# LCs.net
KiCad netlist of a schematic drawn in Altium Designer
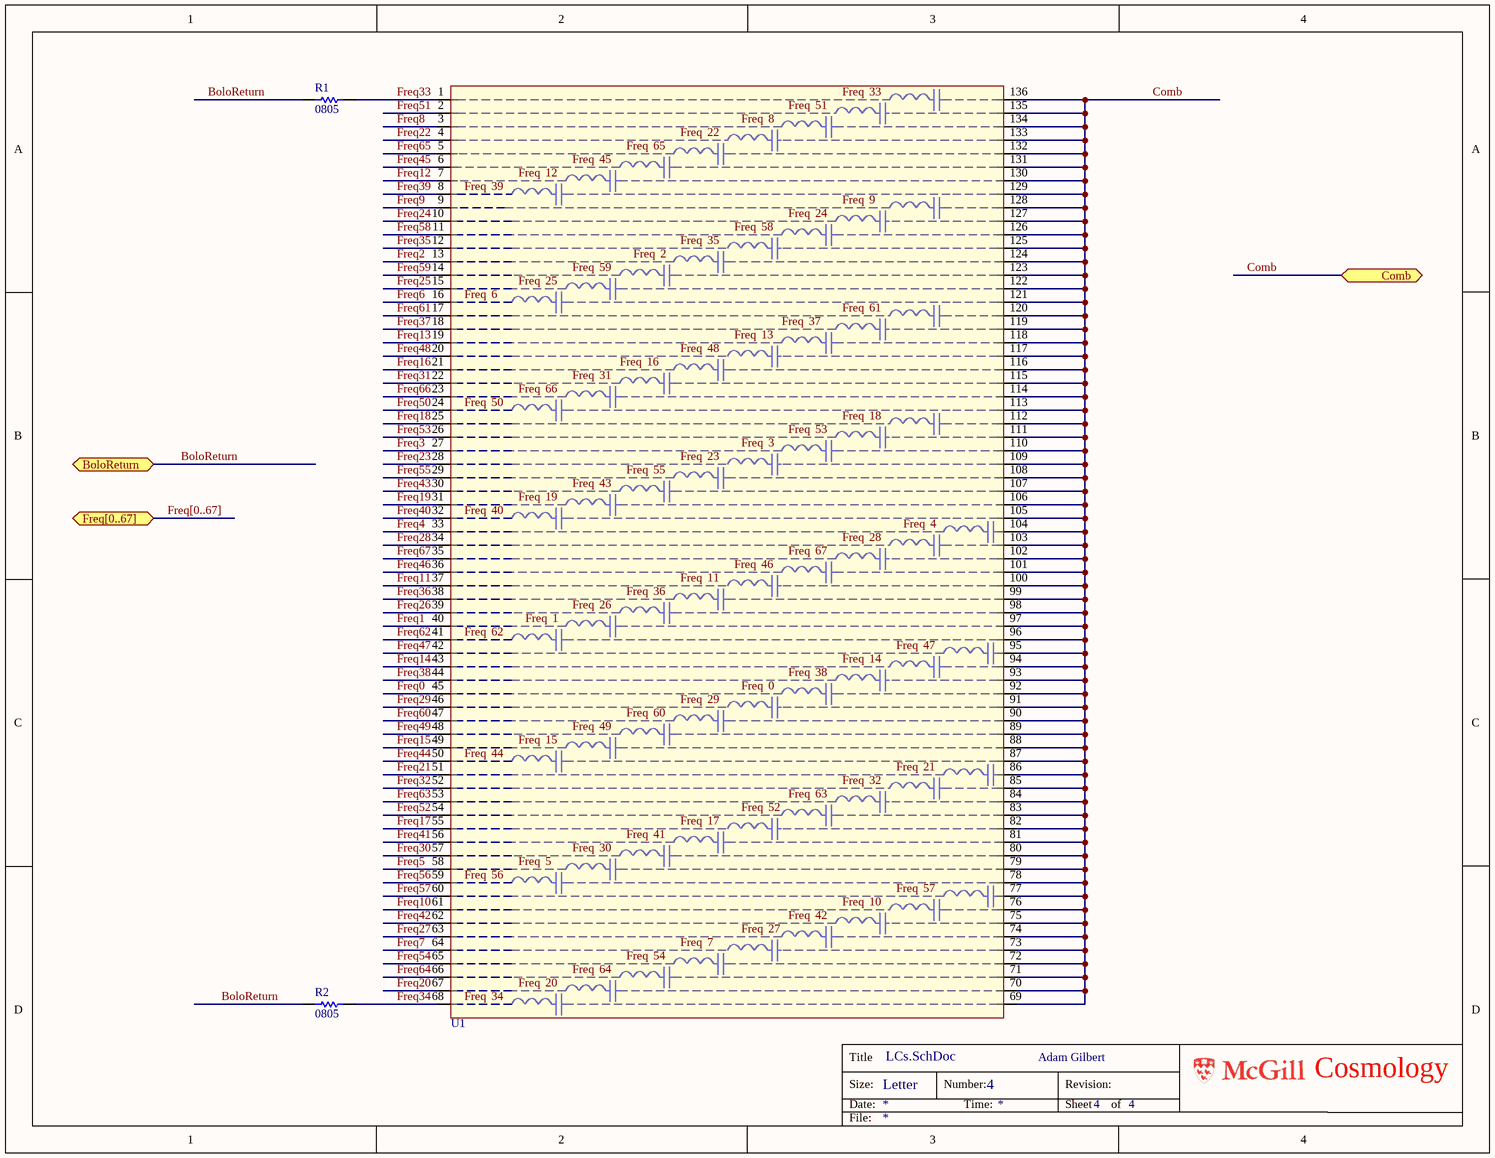
[diagram p0: LCs.SchDoc]

(export (version "E")
  (design (tool "Eeschema 10.0.6"))
  (components
    (comp (ref "R1")
      (value "Res1206")
      (footprint "0805")
      (description "Resistor")
      (libsource (lib "SPT3G_LCBoard") (part "Res1206"))
    )
    (comp (ref "R2")
      (value "Res1206")
      (footprint "0805")
      (description "Resistor")
      (libsource (lib "SPT3G_LCBoard") (part "Res1206"))
    )
    (comp (ref "U1")
      (value "LC68_wafer")
      (footprint "68xLC")
      (description "Gold bonded integrated LC")
      (libsource (lib "SPT3G_LCBoard") (part "LC68Wafer"))
    )
  )
  (nets
    (net (code "1") (name "/BoloReturn") (class "Default")
      (node (ref "R1") (pin "1") (pinfunction "1_1") (pintype "passive"))
      (node (ref "R2") (pin "1") (pinfunction "1_1") (pintype "passive"))
    )
    (net (code "2") (name "/Comb") (class "Default")
      (node (ref "U1") (pin "100") (pinfunction "100_100") (pintype "passive"))
      (node (ref "U1") (pin "101") (pinfunction "101_101") (pintype "passive"))
      (node (ref "U1") (pin "102") (pinfunction "102_102") (pintype "passive"))
      (node (ref "U1") (pin "103") (pinfunction "103_103") (pintype "passive"))
      (node (ref "U1") (pin "104") (pinfunction "104_104") (pintype "passive"))
      (node (ref "U1") (pin "105") (pinfunction "105_105") (pintype "passive"))
      (node (ref "U1") (pin "106") (pinfunction "106_106") (pintype "passive"))
      (node (ref "U1") (pin "107") (pinfunction "107_107") (pintype "passive"))
      (node (ref "U1") (pin "108") (pinfunction "108_108") (pintype "passive"))
      (node (ref "U1") (pin "109") (pinfunction "109_109") (pintype "passive"))
      (node (ref "U1") (pin "110") (pinfunction "110_110") (pintype "passive"))
      (node (ref "U1") (pin "111") (pinfunction "111_111") (pintype "passive"))
      (node (ref "U1") (pin "112") (pinfunction "112_112") (pintype "passive"))
      (node (ref "U1") (pin "113") (pinfunction "113_113") (pintype "passive"))
      (node (ref "U1") (pin "114") (pinfunction "114_114") (pintype "passive"))
      (node (ref "U1") (pin "115") (pinfunction "115_115") (pintype "passive"))
      (node (ref "U1") (pin "116") (pinfunction "116_116") (pintype "passive"))
      (node (ref "U1") (pin "117") (pinfunction "117_117") (pintype "passive"))
      (node (ref "U1") (pin "118") (pinfunction "118_118") (pintype "passive"))
      (node (ref "U1") (pin "119") (pinfunction "119_119") (pintype "passive"))
      (node (ref "U1") (pin "120") (pinfunction "120_120") (pintype "passive"))
      (node (ref "U1") (pin "121") (pinfunction "121_121") (pintype "passive"))
      (node (ref "U1") (pin "122") (pinfunction "122_122") (pintype "passive"))
      (node (ref "U1") (pin "123") (pinfunction "123_123") (pintype "passive"))
      (node (ref "U1") (pin "124") (pinfunction "124_124") (pintype "passive"))
      (node (ref "U1") (pin "125") (pinfunction "125_125") (pintype "passive"))
      (node (ref "U1") (pin "126") (pinfunction "126_126") (pintype "passive"))
      (node (ref "U1") (pin "127") (pinfunction "127_127") (pintype "passive"))
      (node (ref "U1") (pin "128") (pinfunction "128_128") (pintype "passive"))
      (node (ref "U1") (pin "129") (pinfunction "129_129") (pintype "passive"))
      (node (ref "U1") (pin "130") (pinfunction "130_130") (pintype "passive"))
      (node (ref "U1") (pin "131") (pinfunction "131_131") (pintype "passive"))
      (node (ref "U1") (pin "132") (pinfunction "132_132") (pintype "passive"))
      (node (ref "U1") (pin "133") (pinfunction "133_133") (pintype "passive"))
      (node (ref "U1") (pin "134") (pinfunction "134_134") (pintype "passive"))
      (node (ref "U1") (pin "135") (pinfunction "135_135") (pintype "passive"))
      (node (ref "U1") (pin "136") (pinfunction "136_136") (pintype "passive"))
      (node (ref "U1") (pin "69") (pinfunction "69_69") (pintype "passive"))
      (node (ref "U1") (pin "70") (pinfunction "70_70") (pintype "passive"))
      (node (ref "U1") (pin "71") (pinfunction "71_71") (pintype "passive"))
      (node (ref "U1") (pin "72") (pinfunction "72_72") (pintype "passive"))
      (node (ref "U1") (pin "73") (pinfunction "73_73") (pintype "passive"))
      (node (ref "U1") (pin "74") (pinfunction "74_74") (pintype "passive"))
      (node (ref "U1") (pin "75") (pinfunction "75_75") (pintype "passive"))
      (node (ref "U1") (pin "76") (pinfunction "76_76") (pintype "passive"))
      (node (ref "U1") (pin "77") (pinfunction "77_77") (pintype "passive"))
      (node (ref "U1") (pin "78") (pinfunction "78_78") (pintype "passive"))
      (node (ref "U1") (pin "79") (pinfunction "79_79") (pintype "passive"))
      (node (ref "U1") (pin "80") (pinfunction "80_80") (pintype "passive"))
      (node (ref "U1") (pin "81") (pinfunction "81_81") (pintype "passive"))
      (node (ref "U1") (pin "82") (pinfunction "82_82") (pintype "passive"))
      (node (ref "U1") (pin "83") (pinfunction "83_83") (pintype "passive"))
      (node (ref "U1") (pin "84") (pinfunction "84_84") (pintype "passive"))
      (node (ref "U1") (pin "85") (pinfunction "85_85") (pintype "passive"))
      (node (ref "U1") (pin "86") (pinfunction "86_86") (pintype "passive"))
      (node (ref "U1") (pin "87") (pinfunction "87_87") (pintype "passive"))
      (node (ref "U1") (pin "88") (pinfunction "88_88") (pintype "passive"))
      (node (ref "U1") (pin "89") (pinfunction "89_89") (pintype "passive"))
      (node (ref "U1") (pin "90") (pinfunction "90_90") (pintype "passive"))
      (node (ref "U1") (pin "91") (pinfunction "91_91") (pintype "passive"))
      (node (ref "U1") (pin "92") (pinfunction "92_92") (pintype "passive"))
      (node (ref "U1") (pin "93") (pinfunction "93_93") (pintype "passive"))
      (node (ref "U1") (pin "94") (pinfunction "94_94") (pintype "passive"))
      (node (ref "U1") (pin "95") (pinfunction "95_95") (pintype "passive"))
      (node (ref "U1") (pin "96") (pinfunction "96_96") (pintype "passive"))
      (node (ref "U1") (pin "97") (pinfunction "97_97") (pintype "passive"))
      (node (ref "U1") (pin "98") (pinfunction "98_98") (pintype "passive"))
      (node (ref "U1") (pin "99") (pinfunction "99_99") (pintype "passive"))
    )
    (net (code "3") (name "/Freq0") (class "Default")
      (node (ref "U1") (pin "45") (pinfunction "45_45") (pintype "passive"))
    )
    (net (code "4") (name "/Freq1") (class "Default")
      (node (ref "U1") (pin "40") (pinfunction "40_40") (pintype "passive"))
    )
    (net (code "5") (name "/Freq2") (class "Default")
      (node (ref "U1") (pin "13") (pinfunction "13_13") (pintype "passive"))
    )
    (net (code "6") (name "/Freq3") (class "Default")
      (node (ref "U1") (pin "27") (pinfunction "27_27") (pintype "passive"))
    )
    (net (code "7") (name "/Freq4") (class "Default")
      (node (ref "U1") (pin "33") (pinfunction "33_33") (pintype "passive"))
    )
    (net (code "8") (name "/Freq5") (class "Default")
      (node (ref "U1") (pin "58") (pinfunction "58_58") (pintype "passive"))
    )
    (net (code "9") (name "/Freq6") (class "Default")
      (node (ref "U1") (pin "16") (pinfunction "16_16") (pintype "passive"))
    )
    (net (code "10") (name "/Freq7") (class "Default")
      (node (ref "U1") (pin "64") (pinfunction "64_64") (pintype "passive"))
    )
    (net (code "11") (name "/Freq8") (class "Default")
      (node (ref "U1") (pin "3") (pinfunction "3_3") (pintype "passive"))
    )
    (net (code "12") (name "/Freq9") (class "Default")
      (node (ref "U1") (pin "9") (pinfunction "9_9") (pintype "passive"))
    )
    (net (code "13") (name "/Freq10") (class "Default")
      (node (ref "U1") (pin "61") (pinfunction "61_61") (pintype "passive"))
    )
    (net (code "14") (name "/Freq11") (class "Default")
      (node (ref "U1") (pin "37") (pinfunction "37_37") (pintype "passive"))
    )
    (net (code "15") (name "/Freq12") (class "Default")
      (node (ref "U1") (pin "7") (pinfunction "7_7") (pintype "passive"))
    )
    (net (code "16") (name "/Freq13") (class "Default")
      (node (ref "U1") (pin "19") (pinfunction "19_19") (pintype "passive"))
    )
    (net (code "17") (name "/Freq14") (class "Default")
      (node (ref "U1") (pin "43") (pinfunction "43_43") (pintype "passive"))
    )
    (net (code "18") (name "/Freq15") (class "Default")
      (node (ref "U1") (pin "49") (pinfunction "49_49") (pintype "passive"))
    )
    (net (code "19") (name "/Freq16") (class "Default")
      (node (ref "U1") (pin "21") (pinfunction "21_21") (pintype "passive"))
    )
    (net (code "20") (name "/Freq17") (class "Default")
      (node (ref "U1") (pin "55") (pinfunction "55_55") (pintype "passive"))
    )
    (net (code "21") (name "/Freq18") (class "Default")
      (node (ref "U1") (pin "25") (pinfunction "25_25") (pintype "passive"))
    )
    (net (code "22") (name "/Freq19") (class "Default")
      (node (ref "U1") (pin "31") (pinfunction "31_31") (pintype "passive"))
    )
    (net (code "23") (name "/Freq20") (class "Default")
      (node (ref "U1") (pin "67") (pinfunction "67_67") (pintype "passive"))
    )
    (net (code "24") (name "/Freq21") (class "Default")
      (node (ref "U1") (pin "51") (pinfunction "51_51") (pintype "passive"))
    )
    (net (code "25") (name "/Freq22") (class "Default")
      (node (ref "U1") (pin "4") (pinfunction "4_4") (pintype "passive"))
    )
    (net (code "26") (name "/Freq23") (class "Default")
      (node (ref "U1") (pin "28") (pinfunction "28_28") (pintype "passive"))
    )
    (net (code "27") (name "/Freq24") (class "Default")
      (node (ref "U1") (pin "10") (pinfunction "10_10") (pintype "passive"))
    )
    (net (code "28") (name "/Freq25") (class "Default")
      (node (ref "U1") (pin "15") (pinfunction "15_15") (pintype "passive"))
    )
    (net (code "29") (name "/Freq26") (class "Default")
      (node (ref "U1") (pin "39") (pinfunction "39_39") (pintype "passive"))
    )
    (net (code "30") (name "/Freq27") (class "Default")
      (node (ref "U1") (pin "63") (pinfunction "63_63") (pintype "passive"))
    )
    (net (code "31") (name "/Freq28") (class "Default")
      (node (ref "U1") (pin "34") (pinfunction "34_34") (pintype "passive"))
    )
    (net (code "32") (name "/Freq29") (class "Default")
      (node (ref "U1") (pin "46") (pinfunction "46_46") (pintype "passive"))
    )
    (net (code "33") (name "/Freq30") (class "Default")
      (node (ref "U1") (pin "57") (pinfunction "57_57") (pintype "passive"))
    )
    (net (code "34") (name "/Freq31") (class "Default")
      (node (ref "U1") (pin "22") (pinfunction "22_22") (pintype "passive"))
    )
    (net (code "35") (name "/Freq32") (class "Default")
      (node (ref "U1") (pin "52") (pinfunction "52_52") (pintype "passive"))
    )
    (net (code "36") (name "/Freq33") (class "Default")
      (node (ref "R1") (pin "2") (pinfunction "2_2") (pintype "passive"))
      (node (ref "U1") (pin "1") (pinfunction "1_1") (pintype "passive"))
    )
    (net (code "37") (name "/Freq34") (class "Default")
      (node (ref "R2") (pin "2") (pinfunction "2_2") (pintype "passive"))
      (node (ref "U1") (pin "68") (pinfunction "68_68") (pintype "passive"))
    )
    (net (code "38") (name "/Freq35") (class "Default")
      (node (ref "U1") (pin "12") (pinfunction "12_12") (pintype "passive"))
    )
    (net (code "39") (name "/Freq36") (class "Default")
      (node (ref "U1") (pin "38") (pinfunction "38_38") (pintype "passive"))
    )
    (net (code "40") (name "/Freq37") (class "Default")
      (node (ref "U1") (pin "18") (pinfunction "18_18") (pintype "passive"))
    )
    (net (code "41") (name "/Freq38") (class "Default")
      (node (ref "U1") (pin "44") (pinfunction "44_44") (pintype "passive"))
    )
    (net (code "42") (name "/Freq39") (class "Default")
      (node (ref "U1") (pin "8") (pinfunction "8_8") (pintype "passive"))
    )
    (net (code "43") (name "/Freq40") (class "Default")
      (node (ref "U1") (pin "32") (pinfunction "32_32") (pintype "passive"))
    )
    (net (code "44") (name "/Freq41") (class "Default")
      (node (ref "U1") (pin "56") (pinfunction "56_56") (pintype "passive"))
    )
    (net (code "45") (name "/Freq42") (class "Default")
      (node (ref "U1") (pin "62") (pinfunction "62_62") (pintype "passive"))
    )
    (net (code "46") (name "/Freq43") (class "Default")
      (node (ref "U1") (pin "30") (pinfunction "30_30") (pintype "passive"))
    )
    (net (code "47") (name "/Freq44") (class "Default")
      (node (ref "U1") (pin "50") (pinfunction "50_50") (pintype "passive"))
    )
    (net (code "48") (name "/Freq45") (class "Default")
      (node (ref "U1") (pin "6") (pinfunction "6_6") (pintype "passive"))
    )
    (net (code "49") (name "/Freq46") (class "Default")
      (node (ref "U1") (pin "36") (pinfunction "36_36") (pintype "passive"))
    )
    (net (code "50") (name "/Freq47") (class "Default")
      (node (ref "U1") (pin "42") (pinfunction "42_42") (pintype "passive"))
    )
    (net (code "51") (name "/Freq48") (class "Default")
      (node (ref "U1") (pin "20") (pinfunction "20_20") (pintype "passive"))
    )
    (net (code "52") (name "/Freq49") (class "Default")
      (node (ref "U1") (pin "48") (pinfunction "48_48") (pintype "passive"))
    )
    (net (code "53") (name "/Freq50") (class "Default")
      (node (ref "U1") (pin "24") (pinfunction "24_24") (pintype "passive"))
    )
    (net (code "54") (name "/Freq51") (class "Default")
      (node (ref "U1") (pin "2") (pinfunction "2_2") (pintype "passive"))
    )
    (net (code "55") (name "/Freq52") (class "Default")
      (node (ref "U1") (pin "54") (pinfunction "54_54") (pintype "passive"))
    )
    (net (code "56") (name "/Freq53") (class "Default")
      (node (ref "U1") (pin "26") (pinfunction "26_26") (pintype "passive"))
    )
    (net (code "57") (name "/Freq54") (class "Default")
      (node (ref "U1") (pin "65") (pinfunction "65_65") (pintype "passive"))
    )
    (net (code "58") (name "/Freq55") (class "Default")
      (node (ref "U1") (pin "29") (pinfunction "29_29") (pintype "passive"))
    )
    (net (code "59") (name "/Freq56") (class "Default")
      (node (ref "U1") (pin "59") (pinfunction "59_59") (pintype "passive"))
    )
    (net (code "60") (name "/Freq57") (class "Default")
      (node (ref "U1") (pin "60") (pinfunction "60_60") (pintype "passive"))
    )
    (net (code "61") (name "/Freq58") (class "Default")
      (node (ref "U1") (pin "11") (pinfunction "11_11") (pintype "passive"))
    )
    (net (code "62") (name "/Freq59") (class "Default")
      (node (ref "U1") (pin "14") (pinfunction "14_14") (pintype "passive"))
    )
    (net (code "63") (name "/Freq60") (class "Default")
      (node (ref "U1") (pin "47") (pinfunction "47_47") (pintype "passive"))
    )
    (net (code "64") (name "/Freq61") (class "Default")
      (node (ref "U1") (pin "17") (pinfunction "17_17") (pintype "passive"))
    )
    (net (code "65") (name "/Freq62") (class "Default")
      (node (ref "U1") (pin "41") (pinfunction "41_41") (pintype "passive"))
    )
    (net (code "66") (name "/Freq63") (class "Default")
      (node (ref "U1") (pin "53") (pinfunction "53_53") (pintype "passive"))
    )
    (net (code "67") (name "/Freq64") (class "Default")
      (node (ref "U1") (pin "66") (pinfunction "66_66") (pintype "passive"))
    )
    (net (code "68") (name "/Freq65") (class "Default")
      (node (ref "U1") (pin "5") (pinfunction "5_5") (pintype "passive"))
    )
    (net (code "69") (name "/Freq66") (class "Default")
      (node (ref "U1") (pin "23") (pinfunction "23_23") (pintype "passive"))
    )
    (net (code "70") (name "/Freq67") (class "Default")
      (node (ref "U1") (pin "35") (pinfunction "35_35") (pintype "passive"))
    )
  )
)
